# blink1mk3_005t3.net
KiCad netlist of a schematic drawn in EAGLE
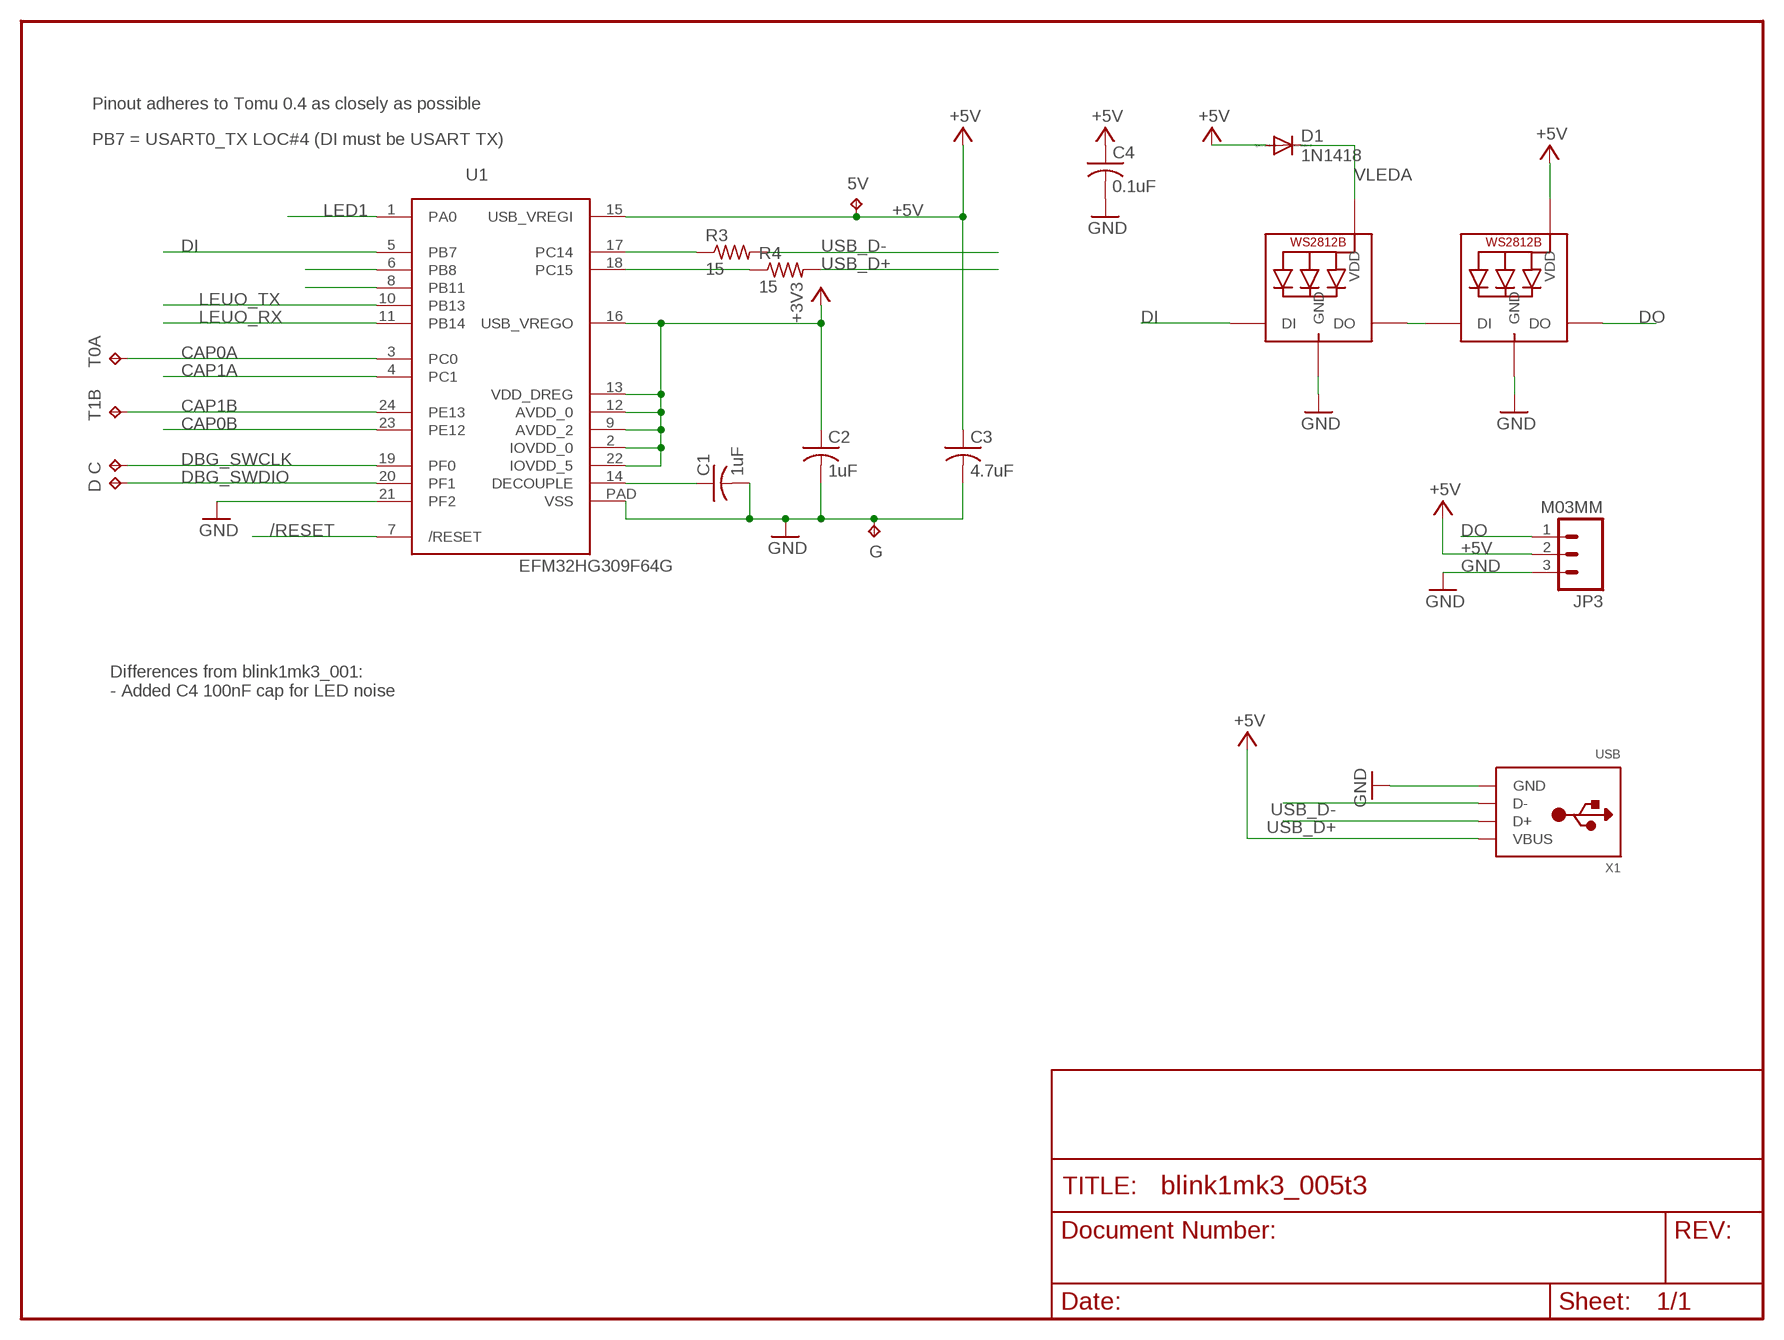
[diagram p0: schematic, sheet 1]

(export (version "E")
  (design (tool "Eeschema 10.0.6"))
  (components
    (comp (ref "5V")
      (value "TPTP10R")
      (footprint "eagle-import:TP10R")
      (libsource (lib "eagle-import") (part "TPTP10R"))
    )
    (comp (ref "C")
      (value "TPTP10R")
      (footprint "eagle-import:TP10R")
      (libsource (lib "eagle-import") (part "TPTP10R"))
    )
    (comp (ref "C1")
      (value "1uF")
      (footprint "eagle-import:C0402")
      (libsource (lib "eagle-import") (part "C-USC0402"))
    )
    (comp (ref "C2")
      (value "1uF")
      (footprint "eagle-import:C0402")
      (libsource (lib "eagle-import") (part "C-USC0402"))
    )
    (comp (ref "C3")
      (value "4.7uF")
      (footprint "eagle-import:C0402")
      (libsource (lib "eagle-import") (part "C-USC0402"))
    )
    (comp (ref "C4")
      (value "0.1uF")
      (footprint "eagle-import:C0402")
      (libsource (lib "eagle-import") (part "C-USC0402"))
    )
    (comp (ref "D")
      (value "TPTP10R")
      (footprint "eagle-import:TP10R")
      (libsource (lib "eagle-import") (part "TPTP10R"))
    )
    (comp (ref "D1")
      (value "1N1418")
      (footprint "eagle-import:SOD523")
      (libsource (lib "eagle-import") (part "DIODE-SOD523"))
    )
    (comp (ref "G")
      (value "TPTP10R")
      (footprint "eagle-import:TP10R")
      (libsource (lib "eagle-import") (part "TPTP10R"))
    )
    (comp (ref "JP3")
      (value "M03MM")
      (footprint "eagle-import:1X03-1.5MM")
      (libsource (lib "eagle-import") (part "M03MM"))
    )
    (comp (ref "LED1")
      (value "SK6812MINI")
      (footprint "eagle-import:LED3535")
      (libsource (lib "eagle-import") (part "WS2812B3535"))
    )
    (comp (ref "LED2")
      (value "SK6812MINI")
      (footprint "eagle-import:LED3535")
      (libsource (lib "eagle-import") (part "WS2812B3535"))
    )
    (comp (ref "R3")
      (value "15")
      (footprint "eagle-import:R0402")
      (libsource (lib "eagle-import") (part "R-US_R0402"))
    )
    (comp (ref "R4")
      (value "15")
      (footprint "eagle-import:R0402")
      (libsource (lib "eagle-import") (part "R-US_R0402"))
    )
    (comp (ref "T0A")
      (value "TPTP10R")
      (footprint "eagle-import:TP10R")
      (libsource (lib "eagle-import") (part "TPTP10R"))
    )
    (comp (ref "T1B")
      (value "TPTP10R")
      (footprint "eagle-import:TP10R")
      (libsource (lib "eagle-import") (part "TPTP10R"))
    )
    (comp (ref "U1")
      (value "EFM32HG309F64G")
      (footprint "eagle-import:QFN24PAD")
      (libsource (lib "eagle-import") (part "EFM32HG309F64G"))
    )
    (comp (ref "X1")
      (value "USB")
      (footprint "eagle-import:MOLEX-48037-1000")
      (libsource (lib "eagle-import") (part "USB"))
    )
  )
  (nets
    (net (code "1") (name "+3V3") (class "Default")
      (node (ref "C2") (pin "1") (pinfunction "1_1") (pintype "passive"))
      (node (ref "U1") (pin "12") (pinfunction "AVDD_0_12") (pintype "bidirectional"))
      (node (ref "U1") (pin "13") (pinfunction "VDD_DREG_13") (pintype "bidirectional"))
      (node (ref "U1") (pin "16") (pinfunction "USB_VREGO_16") (pintype "bidirectional"))
      (node (ref "U1") (pin "2") (pinfunction "IOVDD_0_2") (pintype "bidirectional"))
      (node (ref "U1") (pin "22") (pinfunction "IOVDD_5_22") (pintype "bidirectional"))
      (node (ref "U1") (pin "9") (pinfunction "AVDD_2_9") (pintype "bidirectional"))
    )
    (net (code "2") (name "+5V") (class "Default")
      (node (ref "5V") (pin "TP") (pinfunction "TP_TP") (pintype "input"))
      (node (ref "C3") (pin "1") (pinfunction "1_1") (pintype "passive"))
      (node (ref "C4") (pin "1") (pinfunction "1_1") (pintype "passive"))
      (node (ref "D1") (pin "A") (pinfunction "A_A") (pintype "passive"))
      (node (ref "JP3") (pin "2") (pinfunction "2_2") (pintype "passive"))
      (node (ref "LED2") (pin "2") (pinfunction "VDD_2") (pintype "power_in"))
      (node (ref "U1") (pin "15") (pinfunction "USB_VREGI_15") (pintype "bidirectional"))
      (node (ref "X1") (pin "1") (pinfunction "VBUS_1") (pintype "power_in"))
    )
    (net (code "3") (name "/CAP0A") (class "Default")
      (node (ref "T0A") (pin "TP") (pinfunction "TP_TP") (pintype "input"))
      (node (ref "U1") (pin "3") (pinfunction "PC0_3") (pintype "bidirectional"))
    )
    (net (code "4") (name "/CAP0B") (class "Default")
      (node (ref "U1") (pin "23") (pinfunction "PE12_23") (pintype "bidirectional"))
    )
    (net (code "5") (name "/CAP1A") (class "Default")
      (node (ref "U1") (pin "4") (pinfunction "PC1_4") (pintype "bidirectional"))
    )
    (net (code "6") (name "/CAP1B") (class "Default")
      (node (ref "T1B") (pin "TP") (pinfunction "TP_TP") (pintype "input"))
      (node (ref "U1") (pin "24") (pinfunction "PE13_24") (pintype "bidirectional"))
    )
    (net (code "7") (name "/DBG_SWCLK") (class "Default")
      (node (ref "C") (pin "TP") (pinfunction "TP_TP") (pintype "input"))
      (node (ref "U1") (pin "19") (pinfunction "PF0_19") (pintype "bidirectional"))
    )
    (net (code "8") (name "/DBG_SWDIO") (class "Default")
      (node (ref "D") (pin "TP") (pinfunction "TP_TP") (pintype "input"))
      (node (ref "U1") (pin "20") (pinfunction "PF1_20") (pintype "bidirectional"))
    )
    (net (code "9") (name "/DI") (class "Default")
      (node (ref "LED1") (pin "1") (pinfunction "DI_1") (pintype "input"))
      (node (ref "U1") (pin "5") (pinfunction "PB7_5") (pintype "bidirectional"))
    )
    (net (code "10") (name "/DO") (class "Default")
      (node (ref "JP3") (pin "1") (pinfunction "1_1") (pintype "passive"))
      (node (ref "LED2") (pin "3") (pinfunction "DO_3") (pintype "output"))
    )
    (net (code "11") (name "/LED1") (class "Default")
      (node (ref "U1") (pin "1") (pinfunction "PA0_1") (pintype "bidirectional"))
    )
    (net (code "12") (name "/LEUO_RX") (class "Default")
      (node (ref "U1") (pin "11") (pinfunction "PB14_11") (pintype "bidirectional"))
    )
    (net (code "13") (name "/LEUO_TX") (class "Default")
      (node (ref "U1") (pin "10") (pinfunction "PB13_10") (pintype "bidirectional"))
    )
    (net (code "14") (name "/USB_D+") (class "Default")
      (node (ref "R4") (pin "2") (pinfunction "2_2") (pintype "passive"))
      (node (ref "X1") (pin "3") (pinfunction "D+_3") (pintype "bidirectional"))
    )
    (net (code "15") (name "/USB_D-") (class "Default")
      (node (ref "R3") (pin "2") (pinfunction "2_2") (pintype "passive"))
      (node (ref "X1") (pin "2") (pinfunction "D-_2") (pintype "bidirectional"))
    )
    (net (code "16") (name "/VLEDA") (class "Default")
      (node (ref "D1") (pin "C") (pinfunction "C_C") (pintype "passive"))
      (node (ref "LED1") (pin "2") (pinfunction "VDD_2") (pintype "power_in"))
    )
    (net (code "17") (name "/{slash}RESET") (class "Default")
      (node (ref "U1") (pin "7") (pinfunction "/RESET_7") (pintype "bidirectional"))
    )
    (net (code "18") (name "GND") (class "Default")
      (node (ref "C1") (pin "2") (pinfunction "2_2") (pintype "passive"))
      (node (ref "C2") (pin "2") (pinfunction "2_2") (pintype "passive"))
      (node (ref "C3") (pin "2") (pinfunction "2_2") (pintype "passive"))
      (node (ref "C4") (pin "2") (pinfunction "2_2") (pintype "passive"))
      (node (ref "G") (pin "TP") (pinfunction "TP_TP") (pintype "input"))
      (node (ref "JP3") (pin "3") (pinfunction "3_3") (pintype "passive"))
      (node (ref "LED1") (pin "4") (pinfunction "GND_4") (pintype "power_in"))
      (node (ref "LED2") (pin "4") (pinfunction "GND_4") (pintype "power_in"))
      (node (ref "U1") (pin "21") (pinfunction "PF2_21") (pintype "bidirectional"))
      (node (ref "U1") (pin "PAD") (pinfunction "VSS_PAD") (pintype "bidirectional"))
      (node (ref "X1") (pin "4") (pinfunction "GND_4") (pintype "power_in"))
    )
    (net (code "19") (name "Net-(LED1-DO)") (class "Default")
      (node (ref "LED1") (pin "3") (pinfunction "DO_3") (pintype "output"))
      (node (ref "LED2") (pin "1") (pinfunction "DI_1") (pintype "input"))
    )
    (net (code "20") (name "Net-(U1-DECOUPLE)") (class "Default")
      (node (ref "C1") (pin "1") (pinfunction "1_1") (pintype "passive"))
      (node (ref "U1") (pin "14") (pinfunction "DECOUPLE_14") (pintype "bidirectional"))
    )
    (net (code "21") (name "Net-(U1-PC14)") (class "Default")
      (node (ref "R3") (pin "1") (pinfunction "1_1") (pintype "passive"))
      (node (ref "U1") (pin "17") (pinfunction "PC14_17") (pintype "bidirectional"))
    )
    (net (code "22") (name "Net-(U1-PC15)") (class "Default")
      (node (ref "R4") (pin "1") (pinfunction "1_1") (pintype "passive"))
      (node (ref "U1") (pin "18") (pinfunction "PC15_18") (pintype "bidirectional"))
    )
    (net (code "23") (name "unconnected-(U1-PB8-Pad6)") (class "Default")
      (node (ref "U1") (pin "6") (pinfunction "PB8_6") (pintype "bidirectional"))
    )
    (net (code "24") (name "unconnected-(U1-PB11-Pad8)") (class "Default")
      (node (ref "U1") (pin "8") (pinfunction "PB11_8") (pintype "bidirectional"))
    )
  )
)
